# teensy_driver3.net
KiCad netlist of a schematic drawn in EAGLE
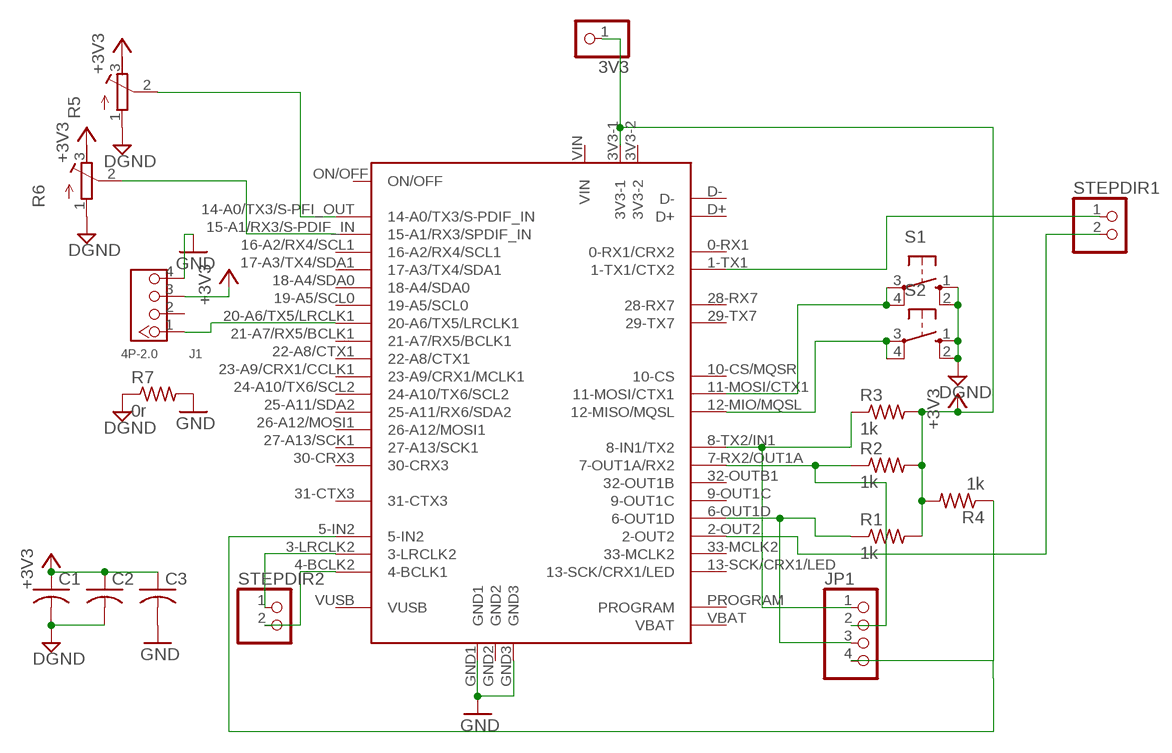
[diagram p0: schematic, sheet 1]

(export (version "E")
  (design (tool "Eeschema 10.0.6"))
  (components
    (comp (ref "3V3")
      (value "PINHD-1X1")
      (footprint "eagle-import:1X01")
      (libsource (lib "eagle-import") (part "PINHD-1X1"))
    )
    (comp (ref "C1")
      (value "C-US025_050-055X075")
      (footprint "eagle-import:C025_050-055X075")
      (libsource (lib "eagle-import") (part "C-US025_050-055X075"))
    )
    (comp (ref "C2")
      (value "C-US025_050-055X075")
      (footprint "eagle-import:C025_050-055X075")
      (libsource (lib "eagle-import") (part "C-US025_050-055X075"))
    )
    (comp (ref "C3")
      (value "C-US025_050-055X075")
      (footprint "eagle-import:C025_050-055X075")
      (libsource (lib "eagle-import") (part "C-US025_050-055X075"))
    )
    (comp (ref "J1")
      (value "4P-2.0")
      (footprint "eagle-import:HW4-2.0")
      (libsource (lib "eagle-import") (part "GROVE-CONNECTOR-DIP(4P-2.0)"))
    )
    (comp (ref "JP1")
      (value "PINHD-1X4")
      (footprint "eagle-import:1X04")
      (libsource (lib "eagle-import") (part "PINHD-1X4"))
    )
    (comp (ref "R1")
      (value "1k")
      (footprint "eagle-import:0207_7")
      (libsource (lib "eagle-import") (part "R-US_0207/7"))
    )
    (comp (ref "R2")
      (value "1k")
      (footprint "eagle-import:0207_7")
      (libsource (lib "eagle-import") (part "R-US_0207/7"))
    )
    (comp (ref "R3")
      (value "1k")
      (footprint "eagle-import:0207_7")
      (libsource (lib "eagle-import") (part "R-US_0207/7"))
    )
    (comp (ref "R4")
      (value "1k")
      (footprint "eagle-import:0207_7")
      (libsource (lib "eagle-import") (part "R-US_0207/7"))
    )
    (comp (ref "R5")
      (value "R-TRIMM74X")
      (footprint "eagle-import:RTRIM74X")
      (libsource (lib "eagle-import") (part "R-TRIMM74X"))
    )
    (comp (ref "R6")
      (value "R-TRIMM74X")
      (footprint "eagle-import:RTRIM74X")
      (libsource (lib "eagle-import") (part "R-TRIMM74X"))
    )
    (comp (ref "R7")
      (value "0r")
      (footprint "eagle-import:0204_7")
      (libsource (lib "eagle-import") (part "R-US_0204/7"))
    )
    (comp (ref "S1")
      (value "10-XX")
      (footprint "eagle-import:B3F-10XX")
      (fields (field (name "MPN") "B3F-1000"))
      (libsource (lib "eagle-import") (part "10-XX"))
    )
    (comp (ref "S2")
      (value "10-XX")
      (footprint "eagle-import:B3F-10XX")
      (fields (field (name "MPN") "B3F-1000"))
      (libsource (lib "eagle-import") (part "10-XX"))
    )
    (comp (ref "STEPDIR1")
      (value "PINHD-1X2")
      (footprint "eagle-import:1X02")
      (libsource (lib "eagle-import") (part "PINHD-1X2"))
    )
    (comp (ref "STEPDIR2")
      (value "PINHD-1X2")
      (footprint "eagle-import:1X02")
      (libsource (lib "eagle-import") (part "PINHD-1X2"))
    )
    (comp (ref "U$1")
      (value "TEENSY40")
      (footprint "eagle-import:TEENSY40")
      (libsource (lib "eagle-import") (part "TEENSY40"))
    )
  )
  (nets
    (net (code "1") (name "+3V3") (class "Default")
      (node (ref "3V3") (pin "1") (pinfunction "1_1") (pintype "passive"))
      (node (ref "C1") (pin "1") (pinfunction "1_1") (pintype "passive"))
      (node (ref "C2") (pin "1") (pinfunction "1_1") (pintype "passive"))
      (node (ref "C3") (pin "1") (pinfunction "1_1") (pintype "passive"))
      (node (ref "J1") (pin "3") (pinfunction "3_3") (pintype "bidirectional"))
      (node (ref "R1") (pin "2") (pinfunction "2_2") (pintype "passive"))
      (node (ref "R2") (pin "2") (pinfunction "2_2") (pintype "passive"))
      (node (ref "R3") (pin "2") (pinfunction "2_2") (pintype "passive"))
      (node (ref "R4") (pin "2") (pinfunction "2_2") (pintype "passive"))
      (node (ref "R5") (pin "3") (pinfunction "E_3") (pintype "passive"))
      (node (ref "R6") (pin "3") (pinfunction "E_3") (pintype "passive"))
      (node (ref "U$1") (pin "3V3-1") (pinfunction "3V3-1_3V3-1") (pintype "bidirectional"))
    )
    (net (code "2") (name "DGND") (class "Default")
      (node (ref "C1") (pin "2") (pinfunction "2_2") (pintype "passive"))
      (node (ref "C2") (pin "2") (pinfunction "2_2") (pintype "passive"))
      (node (ref "R5") (pin "1") (pinfunction "A_1") (pintype "passive"))
      (node (ref "R6") (pin "1") (pinfunction "A_1") (pintype "passive"))
      (node (ref "R7") (pin "1") (pinfunction "1_1") (pintype "passive"))
      (node (ref "S1") (pin "1") (pinfunction "S_1") (pintype "passive"))
      (node (ref "S1") (pin "2") (pinfunction "S1_2") (pintype "passive"))
      (node (ref "S2") (pin "1") (pinfunction "S_1") (pintype "passive"))
      (node (ref "S2") (pin "2") (pinfunction "S1_2") (pintype "passive"))
    )
    (net (code "3") (name "GND") (class "Default")
      (node (ref "C3") (pin "2") (pinfunction "2_2") (pintype "passive"))
      (node (ref "J1") (pin "4") (pinfunction "4_4") (pintype "bidirectional"))
      (node (ref "R7") (pin "2") (pinfunction "2_2") (pintype "passive"))
      (node (ref "U$1") (pin "GND1") (pinfunction "GND1_GND1") (pintype "bidirectional"))
      (node (ref "U$1") (pin "GND3") (pinfunction "GND3_GND3") (pintype "bidirectional"))
    )
    (net (code "4") (name "Net-(J1-Pad1)") (class "Default")
      (node (ref "J1") (pin "1") (pinfunction "1_1") (pintype "bidirectional"))
      (node (ref "U$1") (pin "20-A6/TX5/LRCLK1") (pinfunction "20-A6/TX5/LRCLK1_20-A6/TX5/LRCLK1") (pintype "bidirectional"))
    )
    (net (code "5") (name "Net-(JP1-Pad3)") (class "Default")
      (node (ref "JP1") (pin "3") (pinfunction "3_3") (pintype "passive"))
      (node (ref "R1") (pin "1") (pinfunction "1_1") (pintype "passive"))
      (node (ref "U$1") (pin "6-OUT1D") (pinfunction "6-OUT1D_6-OUT1D") (pintype "bidirectional"))
    )
    (net (code "6") (name "Net-(JP1-Pad4)") (class "Default")
      (node (ref "JP1") (pin "4") (pinfunction "4_4") (pintype "passive"))
      (node (ref "R4") (pin "1") (pinfunction "1_1") (pintype "passive"))
      (node (ref "U$1") (pin "5-IN2") (pinfunction "5-IN2_5-IN2") (pintype "bidirectional"))
    )
    (net (code "7") (name "Net-(R5-S)") (class "Default")
      (node (ref "R5") (pin "2") (pinfunction "S_2") (pintype "passive"))
      (node (ref "U$1") (pin "14-A0/TX3/S-PFI_OUT") (pinfunction "14-A0/TX3/S-PDIF_IN_14-A0/TX3/S-PFI_OUT") (pintype "bidirectional"))
    )
    (net (code "8") (name "Net-(R6-S)") (class "Default")
      (node (ref "R6") (pin "2") (pinfunction "S_2") (pintype "passive"))
      (node (ref "U$1") (pin "15-A1/RX3/S-PDIF_IN") (pinfunction "15-A1/RX3/SPDIF_IN_15-A1/RX3/S-PDIF_IN") (pintype "bidirectional"))
    )
    (net (code "9") (name "Net-(S1-P)") (class "Default")
      (node (ref "S1") (pin "3") (pinfunction "P_3") (pintype "passive"))
      (node (ref "S1") (pin "4") (pinfunction "P1_4") (pintype "passive"))
      (node (ref "U$1") (pin "11-MOSI/CTX1") (pinfunction "11-MOSI/CTX1_11-MOSI/CTX1") (pintype "bidirectional"))
    )
    (net (code "10") (name "Net-(S2-P)") (class "Default")
      (node (ref "S2") (pin "3") (pinfunction "P_3") (pintype "passive"))
      (node (ref "S2") (pin "4") (pinfunction "P1_4") (pintype "passive"))
      (node (ref "U$1") (pin "12-MIO/MQSL") (pinfunction "12-MISO/MQSL_12-MIO/MQSL") (pintype "bidirectional"))
    )
    (net (code "11") (name "Net-(STEPDIR1-Pad2)") (class "Default")
      (node (ref "STEPDIR1") (pin "2") (pinfunction "2_2") (pintype "passive"))
      (node (ref "U$1") (pin "2-OUT2") (pinfunction "2-OUT2_2-OUT2") (pintype "bidirectional"))
    )
    (net (code "12") (name "Net-(STEPDIR2-Pad1)") (class "Default")
      (node (ref "STEPDIR2") (pin "1") (pinfunction "1_1") (pintype "passive"))
      (node (ref "U$1") (pin "3-LRCLK2") (pinfunction "3-LRCLK2_3-LRCLK2") (pintype "bidirectional"))
    )
    (net (code "13") (name "Net-(U$1-1-TX1{slash}CTX2)") (class "Default")
      (node (ref "STEPDIR1") (pin "1") (pinfunction "1_1") (pintype "passive"))
      (node (ref "U$1") (pin "1-TX1") (pinfunction "1-TX1/CTX2_1-TX1") (pintype "bidirectional"))
    )
    (net (code "14") (name "Net-(U$1-4-BCLK1)") (class "Default")
      (node (ref "STEPDIR2") (pin "2") (pinfunction "2_2") (pintype "passive"))
      (node (ref "U$1") (pin "4-BCLK2") (pinfunction "4-BCLK1_4-BCLK2") (pintype "bidirectional"))
    )
    (net (code "15") (name "Net-(U$1-7-OUT1A{slash}RX2)") (class "Default")
      (node (ref "JP1") (pin "2") (pinfunction "2_2") (pintype "passive"))
      (node (ref "R2") (pin "1") (pinfunction "1_1") (pintype "passive"))
      (node (ref "U$1") (pin "7-RX2/OUT1A") (pinfunction "7-OUT1A/RX2_7-RX2/OUT1A") (pintype "bidirectional"))
    )
    (net (code "16") (name "Net-(U$1-8-IN1{slash}TX2)") (class "Default")
      (node (ref "JP1") (pin "1") (pinfunction "1_1") (pintype "passive"))
      (node (ref "R3") (pin "1") (pinfunction "1_1") (pintype "passive"))
      (node (ref "U$1") (pin "8-TX2/IN1") (pinfunction "8-IN1/TX2_8-TX2/IN1") (pintype "bidirectional"))
    )
    (net (code "17") (name "unconnected-(J1-Pad2)") (class "Default")
      (node (ref "J1") (pin "2") (pinfunction "2_2") (pintype "bidirectional"))
    )
    (net (code "18") (name "unconnected-(U$1-0-RX1{slash}CRX2-Pad0-RX1)") (class "Default")
      (node (ref "U$1") (pin "0-RX1") (pinfunction "0-RX1/CRX2_0-RX1") (pintype "bidirectional"))
    )
    (net (code "19") (name "unconnected-(U$1-10-CS-Pad10-CS{slash}MQSR)") (class "Default")
      (node (ref "U$1") (pin "10-CS/MQSR") (pinfunction "10-CS_10-CS/MQSR") (pintype "bidirectional"))
    )
    (net (code "20") (name "unconnected-(U$1-23-A9{slash}CRX1{slash}MCLK1-Pad23-A9{slash}CRX1{slash}CCLK1)") (class "Default")
      (node (ref "U$1") (pin "23-A9/CRX1/CCLK1") (pinfunction "23-A9/CRX1/MCLK1_23-A9/CRX1/CCLK1") (pintype "bidirectional"))
    )
    (net (code "21") (name "unconnected-(U$1-25-A11{slash}RX6{slash}SDA2-Pad25-A11{slash}SDA2)") (class "Default")
      (node (ref "U$1") (pin "25-A11/SDA2") (pinfunction "25-A11/RX6/SDA2_25-A11/SDA2") (pintype "bidirectional"))
    )
    (net (code "22") (name "unconnected-(U$1-32-OUT1B-Pad32-OUTB1)") (class "Default")
      (node (ref "U$1") (pin "32-OUTB1") (pinfunction "32-OUT1B_32-OUTB1") (pintype "bidirectional"))
    )
    (net (code "23") (name "unconnected-(U$1-Pad3V3-2)") (class "Default")
      (node (ref "U$1") (pin "3V3-2") (pinfunction "3V3-2_3V3-2") (pintype "bidirectional"))
    )
    (net (code "24") (name "unconnected-(U$1-Pad9-OUT1C)") (class "Default")
      (node (ref "U$1") (pin "9-OUT1C") (pinfunction "9-OUT1C_9-OUT1C") (pintype "bidirectional"))
    )
    (net (code "25") (name "unconnected-(U$1-Pad13-SCK{slash}CRX1{slash}LED)") (class "Default")
      (node (ref "U$1") (pin "13-SCK/CRX1/LED") (pinfunction "13-SCK/CRX1/LED_13-SCK/CRX1/LED") (pintype "bidirectional"))
    )
    (net (code "26") (name "unconnected-(U$1-Pad16-A2{slash}RX4{slash}SCL1)") (class "Default")
      (node (ref "U$1") (pin "16-A2/RX4/SCL1") (pinfunction "16-A2/RX4/SCL1_16-A2/RX4/SCL1") (pintype "bidirectional"))
    )
    (net (code "27") (name "unconnected-(U$1-Pad17-A3{slash}TX4{slash}SDA1)") (class "Default")
      (node (ref "U$1") (pin "17-A3/TX4/SDA1") (pinfunction "17-A3/TX4/SDA1_17-A3/TX4/SDA1") (pintype "bidirectional"))
    )
    (net (code "28") (name "unconnected-(U$1-Pad18-A4{slash}SDA0)") (class "Default")
      (node (ref "U$1") (pin "18-A4/SDA0") (pinfunction "18-A4/SDA0_18-A4/SDA0") (pintype "bidirectional"))
    )
    (net (code "29") (name "unconnected-(U$1-Pad19-A5{slash}SCL0)") (class "Default")
      (node (ref "U$1") (pin "19-A5/SCL0") (pinfunction "19-A5/SCL0_19-A5/SCL0") (pintype "bidirectional"))
    )
    (net (code "30") (name "unconnected-(U$1-Pad21-A7{slash}RX5{slash}BCLK1)") (class "Default")
      (node (ref "U$1") (pin "21-A7/RX5/BCLK1") (pinfunction "21-A7/RX5/BCLK1_21-A7/RX5/BCLK1") (pintype "bidirectional"))
    )
    (net (code "31") (name "unconnected-(U$1-Pad22-A8{slash}CTX1)") (class "Default")
      (node (ref "U$1") (pin "22-A8/CTX1") (pinfunction "22-A8/CTX1_22-A8/CTX1") (pintype "bidirectional"))
    )
    (net (code "32") (name "unconnected-(U$1-Pad24-A10{slash}TX6{slash}SCL2)") (class "Default")
      (node (ref "U$1") (pin "24-A10/TX6/SCL2") (pinfunction "24-A10/TX6/SCL2_24-A10/TX6/SCL2") (pintype "bidirectional"))
    )
    (net (code "33") (name "unconnected-(U$1-Pad26-A12{slash}MOSI1)") (class "Default")
      (node (ref "U$1") (pin "26-A12/MOSI1") (pinfunction "26-A12/MOSI1_26-A12/MOSI1") (pintype "bidirectional"))
    )
    (net (code "34") (name "unconnected-(U$1-Pad27-A13{slash}SCK1)") (class "Default")
      (node (ref "U$1") (pin "27-A13/SCK1") (pinfunction "27-A13/SCK1_27-A13/SCK1") (pintype "bidirectional"))
    )
    (net (code "35") (name "unconnected-(U$1-Pad28-RX7)") (class "Default")
      (node (ref "U$1") (pin "28-RX7") (pinfunction "28-RX7_28-RX7") (pintype "bidirectional"))
    )
    (net (code "36") (name "unconnected-(U$1-Pad29-TX7)") (class "Default")
      (node (ref "U$1") (pin "29-TX7") (pinfunction "29-TX7_29-TX7") (pintype "bidirectional"))
    )
    (net (code "37") (name "unconnected-(U$1-Pad30-CRX3)") (class "Default")
      (node (ref "U$1") (pin "30-CRX3") (pinfunction "30-CRX3_30-CRX3") (pintype "bidirectional"))
    )
    (net (code "38") (name "unconnected-(U$1-Pad31-CTX3)") (class "Default")
      (node (ref "U$1") (pin "31-CTX3") (pinfunction "31-CTX3_31-CTX3") (pintype "bidirectional"))
    )
    (net (code "39") (name "unconnected-(U$1-Pad33-MCLK2)") (class "Default")
      (node (ref "U$1") (pin "33-MCLK2") (pinfunction "33-MCLK2_33-MCLK2") (pintype "bidirectional"))
    )
    (net (code "40") (name "unconnected-(U$1-PadD+)") (class "Default")
      (node (ref "U$1") (pin "D+") (pinfunction "D+_D+") (pintype "bidirectional"))
    )
    (net (code "41") (name "unconnected-(U$1-PadD-)") (class "Default")
      (node (ref "U$1") (pin "D-") (pinfunction "D-_D-") (pintype "bidirectional"))
    )
    (net (code "42") (name "unconnected-(U$1-PadGND2)") (class "Default")
      (node (ref "U$1") (pin "GND2") (pinfunction "GND2_GND2") (pintype "bidirectional"))
    )
    (net (code "43") (name "unconnected-(U$1-PadON{slash}OFF)") (class "Default")
      (node (ref "U$1") (pin "ON/OFF") (pinfunction "ON/OFF_ON/OFF") (pintype "bidirectional"))
    )
    (net (code "44") (name "unconnected-(U$1-PadPROGRAM)") (class "Default")
      (node (ref "U$1") (pin "PROGRAM") (pinfunction "PROGRAM_PROGRAM") (pintype "bidirectional"))
    )
    (net (code "45") (name "unconnected-(U$1-PadVBAT)") (class "Default")
      (node (ref "U$1") (pin "VBAT") (pinfunction "VBAT_VBAT") (pintype "bidirectional"))
    )
    (net (code "46") (name "unconnected-(U$1-PadVIN)") (class "Default")
      (node (ref "U$1") (pin "VIN") (pinfunction "VIN_VIN") (pintype "bidirectional"))
    )
    (net (code "47") (name "unconnected-(U$1-PadVUSB)") (class "Default")
      (node (ref "U$1") (pin "VUSB") (pinfunction "VUSB_VUSB") (pintype "bidirectional"))
    )
  )
)
